# adapter-50-100mil-x4.net
KiCad netlist of a schematic drawn in Altium Designer
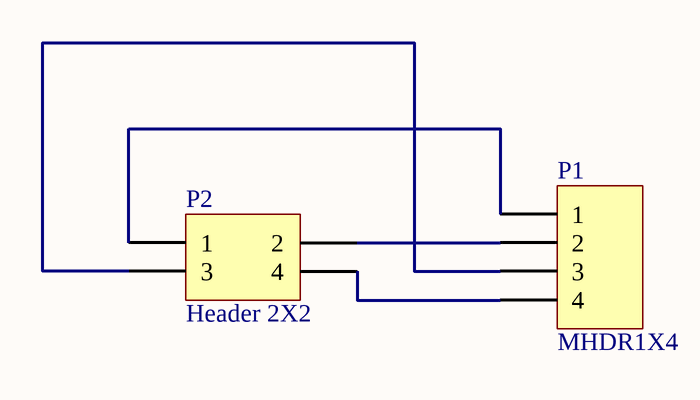
[diagram p0: adapter-50-100mil-x4.SchDoc]

(export (version "E")
  (design (tool "Eeschema 10.0.6"))
  (components
    (comp (ref "P1")
      (value "MHDR1X4")
      (footprint "MHDR1X4")
      (description "Header, 4-Pin")
      (fields (field (name "PUBLISHER") "Altium Limited"))
      (libsource (lib "Miscellaneous Connectors") (part "MHDR1X4"))
    )
    (comp (ref "P2")
      (value "Header 2X2")
      (footprint "HDR2X2")
      (description "Header, 2-Pin, Dual row")
      (fields (field (name "PUBLISHER") "Altium Limited"))
      (libsource (lib "Miscellaneous Connectors") (part "Header 2X2"))
    )
  )
  (nets
    (net (code "1") (name "Net-(P1-Pad1)") (class "Default")
      (node (ref "P1") (pin "1") (pinfunction "1_1") (pintype "passive"))
      (node (ref "P2") (pin "1") (pinfunction "1_1") (pintype "passive"))
    )
    (net (code "2") (name "Net-(P1-Pad2)") (class "Default")
      (node (ref "P1") (pin "2") (pinfunction "2_2") (pintype "passive"))
      (node (ref "P2") (pin "2") (pinfunction "2_2") (pintype "passive"))
    )
    (net (code "3") (name "Net-(P1-Pad3)") (class "Default")
      (node (ref "P1") (pin "3") (pinfunction "3_3") (pintype "passive"))
      (node (ref "P2") (pin "3") (pinfunction "3_3") (pintype "passive"))
    )
    (net (code "4") (name "Net-(P1-Pad4)") (class "Default")
      (node (ref "P1") (pin "4") (pinfunction "4_4") (pintype "passive"))
      (node (ref "P2") (pin "4") (pinfunction "4_4") (pintype "passive"))
    )
  )
)
